# S7CAS-PLEIADES-CARTE-MERE_P20_Motor.net
KiCad netlist of a schematic drawn in Altium Designer
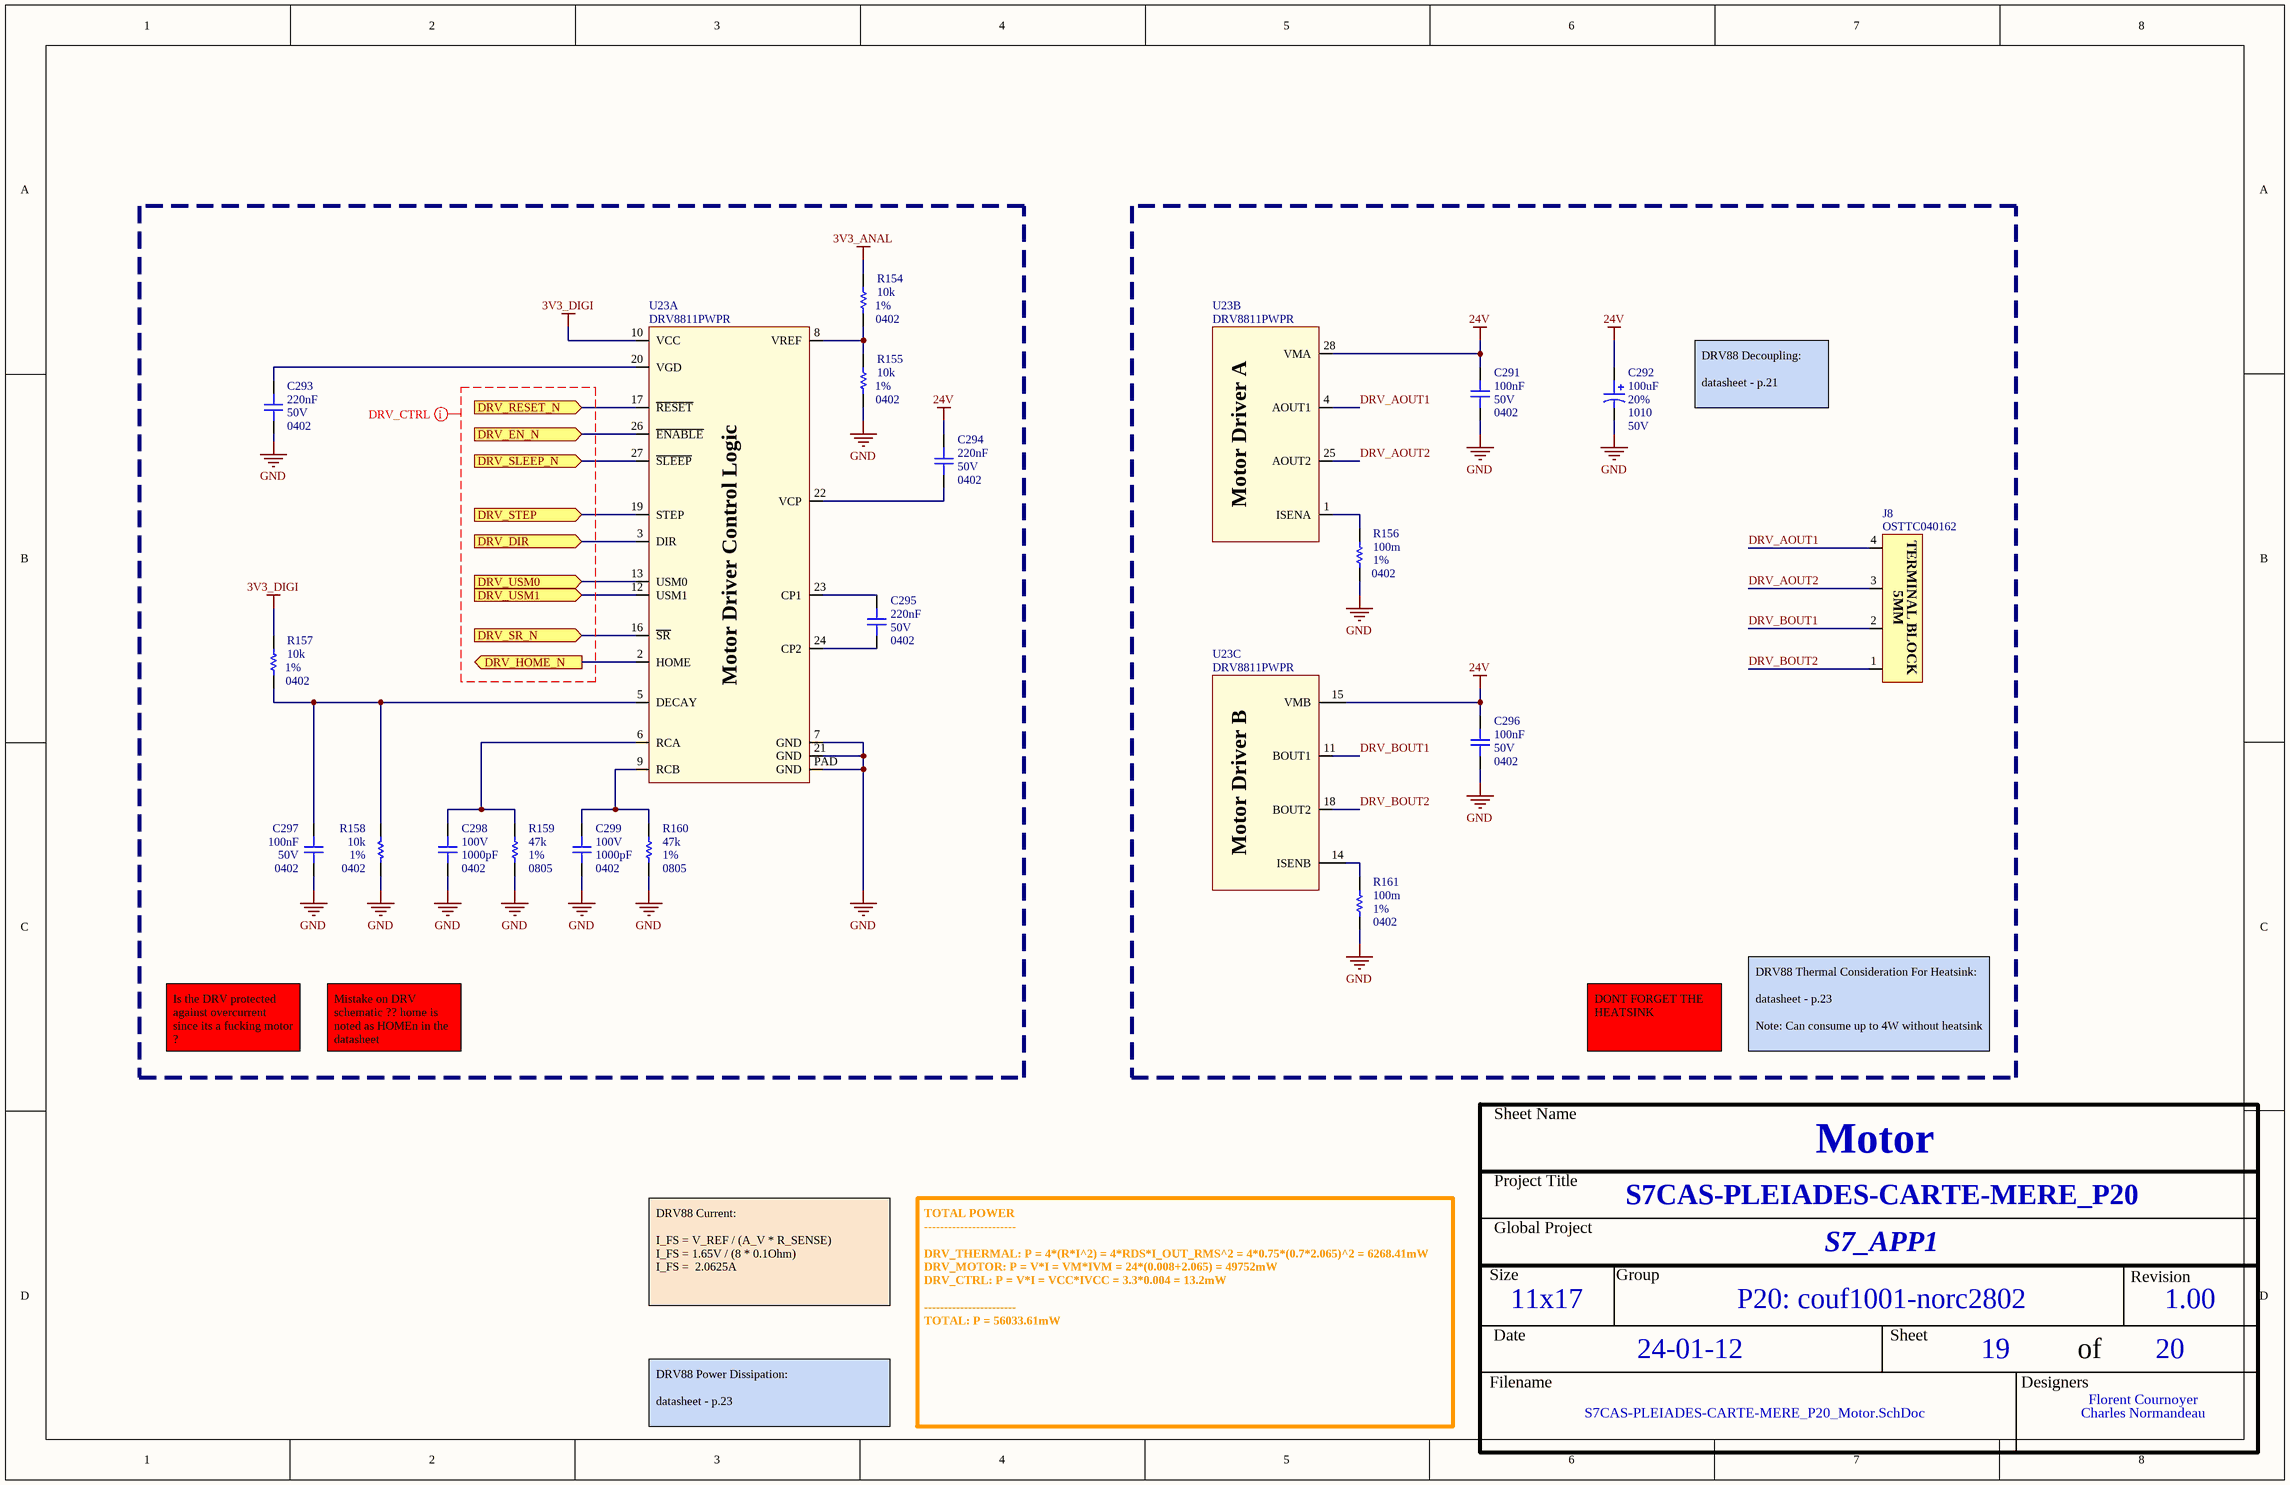
[diagram p0: S7CAS-PLEIADES-CARTE-MERE_P20_Motor.SchDoc]

(export (version "E")
  (design (tool "Eeschema 10.0.6"))
  (components
    (comp (ref "C291")
      (value "100nF")
      (footprint "CAP_0402")
      (description "CAP - 0402")
      (fields
        (field (name "MFG PART NUMBER") "GRM155R61H104KE14")
        (field (name "VOLTAGE") "50V")
        (field (name "PACKAGE") "0402")
        (field (name "CREATEDBY") "Jonathan Bouchard")
      )
      (libsource (lib "S7CAS_LIB2023") (part "CAP - 0402"))
    )
    (comp (ref "C292")
      (value "100uF")
      (footprint "CAP_ALU_1010_vishay")
      (description "CAP - ALU 100uF 20% 50V - 1010")
      (fields
        (field (name "MFG") "Vishay Dale")
        (field (name "MFG PART NUMBER") "MAL215099101E3")
        (field (name "VOLTAGE") "50V")
        (field (name "PACKAGE") "1010")
        (field (name "PRECISION") "20%")
        (field (name "CREATEDBY") "Jonathan Bouchard")
      )
      (libsource (lib "S7CAS_LIB2023") (part "CAP_ALU_MAL215099101E3"))
    )
    (comp (ref "C293")
      (value "220nF")
      (footprint "CAP_0402")
      (description "CAP - 0402")
      (fields
        (field (name "MFG PART NUMBER") "GRM155R61H224KE01")
        (field (name "VOLTAGE") "50V")
        (field (name "PACKAGE") "0402")
        (field (name "CREATEDBY") "Jonathan Bouchard")
      )
      (libsource (lib "S7CAS_LIB2023") (part "CAP - 0402"))
    )
    (comp (ref "C294")
      (value "220nF")
      (footprint "CAP_0402")
      (description "CAP - 0402")
      (fields
        (field (name "MFG PART NUMBER") "GRM155R61H224KE01")
        (field (name "VOLTAGE") "50V")
        (field (name "PACKAGE") "0402")
        (field (name "CREATEDBY") "Jonathan Bouchard")
      )
      (libsource (lib "S7CAS_LIB2023") (part "CAP - 0402"))
    )
    (comp (ref "C295")
      (value "220nF")
      (footprint "CAP_0402")
      (description "CAP - 0402")
      (fields
        (field (name "MFG PART NUMBER") "GRM155R61H224KE01")
        (field (name "VOLTAGE") "50V")
        (field (name "PACKAGE") "0402")
        (field (name "CREATEDBY") "Jonathan Bouchard")
      )
      (libsource (lib "S7CAS_LIB2023") (part "CAP - 0402"))
    )
    (comp (ref "C296")
      (value "100nF")
      (footprint "CAP_0402")
      (description "CAP - 0402")
      (fields
        (field (name "MFG PART NUMBER") "GRM155R61H104KE14")
        (field (name "VOLTAGE") "50V")
        (field (name "PACKAGE") "0402")
        (field (name "CREATEDBY") "Jonathan Bouchard")
      )
      (libsource (lib "S7CAS_LIB2023") (part "CAP - 0402"))
    )
    (comp (ref "C297")
      (value "100nF")
      (footprint "CAP_0402")
      (description "CAP - 0402")
      (fields
        (field (name "MFG PART NUMBER") "GRM155R61H104KE14")
        (field (name "VOLTAGE") "50V")
        (field (name "PACKAGE") "0402")
        (field (name "CREATEDBY") "Jonathan Bouchard")
      )
      (libsource (lib "S7CAS_LIB2023") (part "CAP - 0402"))
    )
    (comp (ref "C298")
      (value "1000pF")
      (footprint "CAP_0402")
      (description "CAP - 0402")
      (fields
        (field (name "MFG PART NUMBER") "GRM155R72A102KA01")
        (field (name "VOLTAGE") "100V")
        (field (name "PACKAGE") "0402")
        (field (name "CREATEDBY") "Jonathan Bouchard")
      )
      (libsource (lib "S7CAS_LIB2023") (part "CAP - 0402"))
    )
    (comp (ref "C299")
      (value "1000pF")
      (footprint "CAP_0402")
      (description "CAP - 0402")
      (fields
        (field (name "MFG PART NUMBER") "GRM155R72A102KA01")
        (field (name "VOLTAGE") "100V")
        (field (name "PACKAGE") "0402")
        (field (name "CREATEDBY") "Jonathan Bouchard")
      )
      (libsource (lib "S7CAS_LIB2023") (part "CAP - 0402"))
    )
    (comp (ref "J8")
      (value "OSTTC040162")
      (footprint "CONN_TERMINAL_OSTTA040161")
      (description "CONN -  TERMINAL BLOCK 4POS 5MM - TH")
      (fields (field (name "MFG") "On Shore Technology Inc.") (field (name "CREATEDBY") "Jonathan Bouchard"))
      (libsource (lib "S7CAS_LIB2023") (part "CONN_TERMINAL_OSTTC040162"))
    )
    (comp (ref "R154")
      (value "10k")
      (footprint "RES_0402")
      (description "RES - 0402")
      (fields
        (field (name "VOLTAGE") "50V")
        (field (name "MFG PART NUMBER") "MCS04020C1002FE000")
        (field (name "PACKAGE") "0402")
        (field (name "PRECISION") "1%")
        (field (name "CREATEDBY") "Jonathan Bouchard")
      )
      (libsource (lib "S7CAS_LIB2023") (part "RES - 0402"))
    )
    (comp (ref "R155")
      (value "10k")
      (footprint "RES_0402")
      (description "RES - 0402")
      (fields
        (field (name "VOLTAGE") "50V")
        (field (name "MFG PART NUMBER") "MCS04020C1002FE000")
        (field (name "PACKAGE") "0402")
        (field (name "PRECISION") "1%")
        (field (name "CREATEDBY") "Jonathan Bouchard")
      )
      (libsource (lib "S7CAS_LIB2023") (part "RES - 0402"))
    )
    (comp (ref "R156")
      (value "100m")
      (footprint "RES_0402")
      (description "RES - 0402")
      (fields
        (field (name "VOLTAGE") "50V")
        (field (name "MFG PART NUMBER") "ERJ-2BWFR100X")
        (field (name "PACKAGE") "0402")
        (field (name "PRECISION") "1%")
        (field (name "CREATEDBY") "Jonathan Bouchard")
      )
      (libsource (lib "S7CAS_LIB2023") (part "RES - 0402"))
    )
    (comp (ref "R157")
      (value "10k")
      (footprint "RES_0402")
      (description "RES - 0402")
      (fields
        (field (name "VOLTAGE") "50V")
        (field (name "MFG PART NUMBER") "MCS04020C1002FE000")
        (field (name "PACKAGE") "0402")
        (field (name "PRECISION") "1%")
        (field (name "CREATEDBY") "Jonathan Bouchard")
      )
      (libsource (lib "S7CAS_LIB2023") (part "RES - 0402"))
    )
    (comp (ref "R158")
      (value "10k")
      (footprint "RES_0402")
      (description "RES - 0402")
      (fields
        (field (name "VOLTAGE") "50V")
        (field (name "MFG PART NUMBER") "MCS04020C1002FE000")
        (field (name "PACKAGE") "0402")
        (field (name "PRECISION") "1%")
        (field (name "CREATEDBY") "Jonathan Bouchard")
      )
      (libsource (lib "S7CAS_LIB2023") (part "RES - 0402"))
    )
    (comp (ref "R159")
      (value "47k")
      (footprint "RES_0402")
      (description "RES - 0402")
      (fields
        (field (name "VOLTAGE") "50V")
        (field (name "MFG PART NUMBER") "CRCW080547K0FKECHP")
        (field (name "PACKAGE") "0805")
        (field (name "PRECISION") "1%")
        (field (name "CREATEDBY") "Jonathan Bouchard")
      )
      (libsource (lib "S7CAS_LIB2023") (part "RES - 0402"))
    )
    (comp (ref "R160")
      (value "47k")
      (footprint "RES_0402")
      (description "RES - 0402")
      (fields
        (field (name "VOLTAGE") "50V")
        (field (name "MFG PART NUMBER") "CRCW080547K0FKECHP")
        (field (name "PACKAGE") "0805")
        (field (name "PRECISION") "1%")
        (field (name "CREATEDBY") "Jonathan Bouchard")
      )
      (libsource (lib "S7CAS_LIB2023") (part "RES - 0402"))
    )
    (comp (ref "R161")
      (value "100m")
      (footprint "RES_0402")
      (description "RES - 0402")
      (fields
        (field (name "VOLTAGE") "50V")
        (field (name "MFG PART NUMBER") "ERJ-2BWFR100X")
        (field (name "PACKAGE") "0402")
        (field (name "PRECISION") "1%")
        (field (name "CREATEDBY") "Jonathan Bouchard")
      )
      (libsource (lib "S7CAS_LIB2023") (part "RES - 0402"))
    )
    (comp (ref "U23")
      (value "DRV8811PWPR")
      (footprint "POW_MOTOR_DRV8811PWPR")
      (description "POW - STEPPER MOTOR DRIVER - SOP-28")
      (fields
        (field (name "VOLTAGE") "3 V ~ 5.5 V / 8 V ~ 38 V")
        (field (name "MFG") "Texas Instrument")
        (field (name "CREATEDBY") "Jonathan Bouchard")
      )
      (libsource (lib "S7CAS_LIB2023") (part "POW_MOTOR_DRV8811PWPR"))
    )
  )
  (nets
    (net (code "1") (name "/DRV_AOUT1") (class "Default")
      (node (ref "J8") (pin "4") (pinfunction "4_4") (pintype "passive"))
      (node (ref "U23") (pin "4") (pinfunction "AOUT1_4") (pintype "passive"))
    )
    (net (code "2") (name "/DRV_AOUT2") (class "Default")
      (node (ref "J8") (pin "3") (pinfunction "3_3") (pintype "passive"))
      (node (ref "U23") (pin "25") (pinfunction "AOUT2_25") (pintype "passive"))
    )
    (net (code "3") (name "/DRV_BOUT1") (class "Default")
      (node (ref "J8") (pin "2") (pinfunction "2_2") (pintype "passive"))
      (node (ref "U23") (pin "11") (pinfunction "BOUT1_11") (pintype "passive"))
    )
    (net (code "4") (name "/DRV_BOUT2") (class "Default")
      (node (ref "J8") (pin "1") (pinfunction "1_1") (pintype "passive"))
      (node (ref "U23") (pin "18") (pinfunction "BOUT2_18") (pintype "passive"))
    )
    (net (code "5") (name "/DRV_DIR") (class "Default")
      (node (ref "U23") (pin "3") (pinfunction "DIR_3") (pintype "passive"))
    )
    (net (code "6") (name "/DRV_EN_N") (class "Default")
      (node (ref "U23") (pin "26") (pinfunction "~{ENABLE}_26") (pintype "passive"))
    )
    (net (code "7") (name "/DRV_HOME_N") (class "Default")
      (node (ref "U23") (pin "2") (pinfunction "HOME_2") (pintype "passive"))
    )
    (net (code "8") (name "/DRV_RESET_N") (class "Default")
      (node (ref "U23") (pin "17") (pinfunction "~{RESET}_17") (pintype "passive"))
    )
    (net (code "9") (name "/DRV_SLEEP_N") (class "Default")
      (node (ref "U23") (pin "27") (pinfunction "~{SLEEP}_27") (pintype "passive"))
    )
    (net (code "10") (name "/DRV_SR_N") (class "Default")
      (node (ref "U23") (pin "16") (pinfunction "~{SR}_16") (pintype "passive"))
    )
    (net (code "11") (name "/DRV_STEP") (class "Default")
      (node (ref "U23") (pin "19") (pinfunction "STEP_19") (pintype "passive"))
    )
    (net (code "12") (name "/DRV_USM0") (class "Default")
      (node (ref "U23") (pin "13") (pinfunction "USM0_13") (pintype "passive"))
    )
    (net (code "13") (name "/DRV_USM1") (class "Default")
      (node (ref "U23") (pin "12") (pinfunction "USM1_12") (pintype "passive"))
    )
    (net (code "14") (name "3V3_ANAL") (class "Default")
      (node (ref "R154") (pin "2") (pinfunction "2_2") (pintype "passive"))
    )
    (net (code "15") (name "3V3_DIGI") (class "Default")
      (node (ref "R157") (pin "2") (pinfunction "2_2") (pintype "passive"))
      (node (ref "U23") (pin "10") (pinfunction "VCC_10") (pintype "passive"))
    )
    (net (code "16") (name "24V") (class "Default")
      (node (ref "C291") (pin "2") (pinfunction "2_2") (pintype "passive"))
      (node (ref "C292") (pin "1") (pinfunction "1_1") (pintype "passive"))
      (node (ref "C294") (pin "2") (pinfunction "2_2") (pintype "passive"))
      (node (ref "C296") (pin "2") (pinfunction "2_2") (pintype "passive"))
      (node (ref "U23") (pin "15") (pinfunction "VMB_15") (pintype "passive"))
      (node (ref "U23") (pin "28") (pinfunction "VMA_28") (pintype "passive"))
    )
    (net (code "17") (name "GND") (class "Default")
      (node (ref "C291") (pin "1") (pinfunction "1_1") (pintype "passive"))
      (node (ref "C292") (pin "2") (pinfunction "2_2") (pintype "passive"))
      (node (ref "C293") (pin "1") (pinfunction "1_1") (pintype "passive"))
      (node (ref "C296") (pin "1") (pinfunction "1_1") (pintype "passive"))
      (node (ref "C297") (pin "1") (pinfunction "1_1") (pintype "passive"))
      (node (ref "C298") (pin "2") (pinfunction "2_2") (pintype "passive"))
      (node (ref "C299") (pin "2") (pinfunction "2_2") (pintype "passive"))
      (node (ref "R155") (pin "1") (pinfunction "1_1") (pintype "passive"))
      (node (ref "R156") (pin "1") (pinfunction "1_1") (pintype "passive"))
      (node (ref "R158") (pin "1") (pinfunction "1_1") (pintype "passive"))
      (node (ref "R159") (pin "1") (pinfunction "1_1") (pintype "passive"))
      (node (ref "R160") (pin "1") (pinfunction "1_1") (pintype "passive"))
      (node (ref "R161") (pin "1") (pinfunction "1_1") (pintype "passive"))
      (node (ref "U23") (pin "21") (pinfunction "GND_21") (pintype "passive"))
      (node (ref "U23") (pin "7") (pinfunction "GND_7") (pintype "passive"))
      (node (ref "U23") (pin "PAD") (pinfunction "GND_PAD") (pintype "passive"))
    )
    (net (code "18") (name "Net-(U23A-CP1)") (class "Default")
      (node (ref "C295") (pin "2") (pinfunction "2_2") (pintype "passive"))
      (node (ref "U23") (pin "23") (pinfunction "CP1_23") (pintype "passive"))
    )
    (net (code "19") (name "Net-(U23A-CP2)") (class "Default")
      (node (ref "C295") (pin "1") (pinfunction "1_1") (pintype "passive"))
      (node (ref "U23") (pin "24") (pinfunction "CP2_24") (pintype "passive"))
    )
    (net (code "20") (name "Net-(U23A-DECAY)") (class "Default")
      (node (ref "C297") (pin "2") (pinfunction "2_2") (pintype "passive"))
      (node (ref "R157") (pin "1") (pinfunction "1_1") (pintype "passive"))
      (node (ref "R158") (pin "2") (pinfunction "2_2") (pintype "passive"))
      (node (ref "U23") (pin "5") (pinfunction "DECAY_5") (pintype "passive"))
    )
    (net (code "21") (name "Net-(U23A-RCA)") (class "Default")
      (node (ref "C298") (pin "1") (pinfunction "1_1") (pintype "passive"))
      (node (ref "R159") (pin "2") (pinfunction "2_2") (pintype "passive"))
      (node (ref "U23") (pin "6") (pinfunction "RCA_6") (pintype "passive"))
    )
    (net (code "22") (name "Net-(U23A-RCB)") (class "Default")
      (node (ref "C299") (pin "1") (pinfunction "1_1") (pintype "passive"))
      (node (ref "R160") (pin "2") (pinfunction "2_2") (pintype "passive"))
      (node (ref "U23") (pin "9") (pinfunction "RCB_9") (pintype "passive"))
    )
    (net (code "23") (name "Net-(U23A-VCP)") (class "Default")
      (node (ref "C294") (pin "1") (pinfunction "1_1") (pintype "passive"))
      (node (ref "U23") (pin "22") (pinfunction "VCP_22") (pintype "passive"))
    )
    (net (code "24") (name "Net-(U23A-VGD)") (class "Default")
      (node (ref "C293") (pin "2") (pinfunction "2_2") (pintype "passive"))
      (node (ref "U23") (pin "20") (pinfunction "VGD_20") (pintype "passive"))
    )
    (net (code "25") (name "Net-(U23A-VREF)") (class "Default")
      (node (ref "R154") (pin "1") (pinfunction "1_1") (pintype "passive"))
      (node (ref "R155") (pin "2") (pinfunction "2_2") (pintype "passive"))
      (node (ref "U23") (pin "8") (pinfunction "VREF_8") (pintype "passive"))
    )
    (net (code "26") (name "Net-(U23B-ISENA)") (class "Default")
      (node (ref "R156") (pin "2") (pinfunction "2_2") (pintype "passive"))
      (node (ref "U23") (pin "1") (pinfunction "ISENA_1") (pintype "passive"))
    )
    (net (code "27") (name "Net-(U23C-ISENB)") (class "Default")
      (node (ref "R161") (pin "2") (pinfunction "2_2") (pintype "passive"))
      (node (ref "U23") (pin "14") (pinfunction "ISENB_14") (pintype "passive"))
    )
  )
)
